# littlerlights.net
KiCad netlist of a schematic drawn in EAGLE
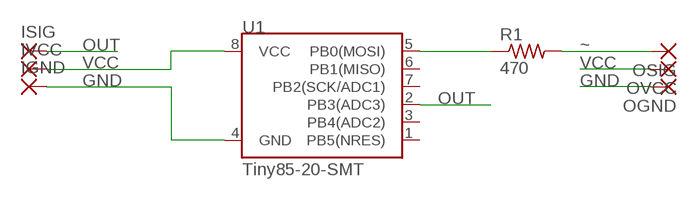
[diagram p0: schematic, sheet 1]

(export (version "E")
  (design (tool "Eeschema 10.0.6"))
  (components
    (comp (ref "IGND")
      (value "SMD2")
      (footprint "eagle-import:SMD1,27-2,54")
      (libsource (lib "eagle-import") (part "SMD2"))
    )
    (comp (ref "ISIG")
      (value "SMD2")
      (footprint "eagle-import:SMD1,27-2,54")
      (libsource (lib "eagle-import") (part "SMD2"))
    )
    (comp (ref "IVCC")
      (value "SMD2")
      (footprint "eagle-import:SMD1,27-2,54")
      (libsource (lib "eagle-import") (part "SMD2"))
    )
    (comp (ref "OGND")
      (value "SMD2")
      (footprint "eagle-import:SMD1,27-2,54")
      (libsource (lib "eagle-import") (part "SMD2"))
    )
    (comp (ref "OSIG")
      (value "SMD2")
      (footprint "eagle-import:SMD1,27-2,54")
      (libsource (lib "eagle-import") (part "SMD2"))
    )
    (comp (ref "OVCC")
      (value "SMD2")
      (footprint "eagle-import:SMD1,27-2,54")
      (libsource (lib "eagle-import") (part "SMD2"))
    )
    (comp (ref "R1")
      (value "470")
      (footprint "eagle-import:R0603")
      (libsource (lib "eagle-import") (part "R-US_R0603"))
    )
    (comp (ref "U1")
      (value "Tiny85-20-SMT")
      (footprint "eagle-import:SO08-EIAJ")
      (libsource (lib "eagle-import") (part "ATTINY45TINY85-20-SMT"))
    )
  )
  (nets
    (net (code "1") (name "/GND") (class "Default")
      (node (ref "IGND") (pin "1") (pinfunction "P_1") (pintype "passive"))
      (node (ref "OGND") (pin "1") (pinfunction "P_1") (pintype "passive"))
      (node (ref "U1") (pin "4") (pinfunction "GND_4") (pintype "bidirectional"))
    )
    (net (code "2") (name "/OUT") (class "Default")
      (node (ref "ISIG") (pin "1") (pinfunction "P_1") (pintype "passive"))
      (node (ref "U1") (pin "2") (pinfunction "PB3(ADC3)_2") (pintype "bidirectional"))
    )
    (net (code "3") (name "/VCC") (class "Default")
      (node (ref "IVCC") (pin "1") (pinfunction "P_1") (pintype "passive"))
      (node (ref "OVCC") (pin "1") (pinfunction "P_1") (pintype "passive"))
      (node (ref "U1") (pin "8") (pinfunction "VCC_8") (pintype "bidirectional"))
    )
    (net (code "4") (name "/~") (class "Default")
      (node (ref "OSIG") (pin "1") (pinfunction "P_1") (pintype "passive"))
      (node (ref "R1") (pin "2") (pinfunction "2_2") (pintype "passive"))
    )
    (net (code "5") (name "Net-(U1-PB0(MOSI))") (class "Default")
      (node (ref "R1") (pin "1") (pinfunction "1_1") (pintype "passive"))
      (node (ref "U1") (pin "5") (pinfunction "PB0(MOSI)_5") (pintype "bidirectional"))
    )
    (net (code "6") (name "unconnected-(U1-PB1(MISO)-Pad6)") (class "Default")
      (node (ref "U1") (pin "6") (pinfunction "PB1(MISO)_6") (pintype "bidirectional"))
    )
    (net (code "7") (name "unconnected-(U1-PB2(SCK{slash}ADC1)-Pad7)") (class "Default")
      (node (ref "U1") (pin "7") (pinfunction "PB2(SCK/ADC1)_7") (pintype "bidirectional"))
    )
    (net (code "8") (name "unconnected-(U1-PB4(ADC2)-Pad3)") (class "Default")
      (node (ref "U1") (pin "3") (pinfunction "PB4(ADC2)_3") (pintype "bidirectional"))
    )
    (net (code "9") (name "unconnected-(U1-PB5(NRES)-Pad1)") (class "Default")
      (node (ref "U1") (pin "1") (pinfunction "PB5(NRES)_1") (pintype "bidirectional"))
    )
  )
)
